# Relay_IO.net
KiCad netlist of a schematic drawn in Altium Designer
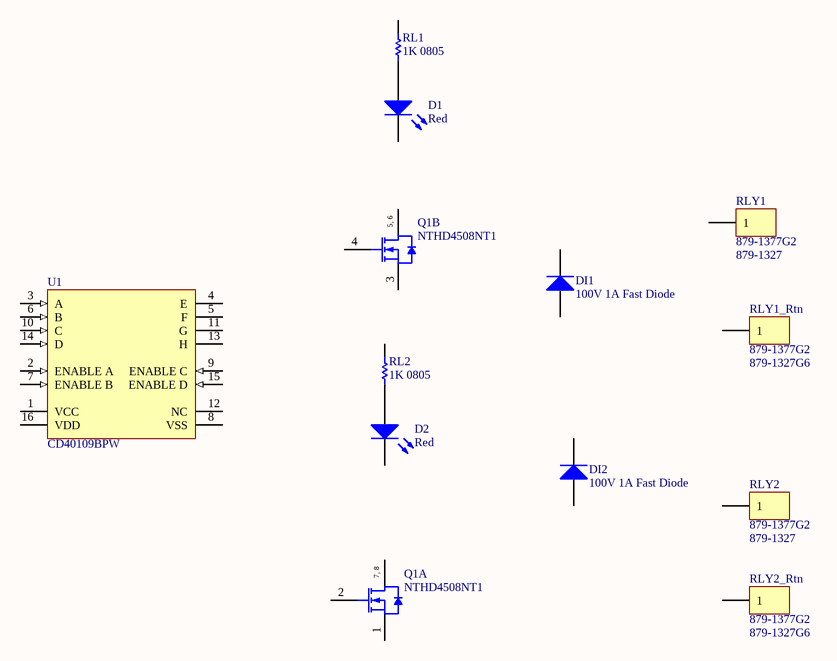
[diagram p0: Relay_IO.SchDoc]

(export (version "E")
  (design (tool "Eeschema 10.0.6"))
  (components
    (comp (ref "D1")
      (value "LED Red")
      (footprint "0603_A")
      (description "SMD mono-color Chip LED, WL-SMCW, Red")
      (fields
        (field (name "MANUFACTURER") "Wurth Electronics Inc")
        (field (name "MANUFACTURER PART NUMBER") "150060RS75000")
        (field (name "COLOR") "Red")
      )
      (libsource (lib "WCT") (part "LED_Red0603"))
    )
    (comp (ref "D2")
      (value "LED Red")
      (footprint "0603_A")
      (description "SMD mono-color Chip LED, WL-SMCW, Red")
      (fields
        (field (name "MANUFACTURER") "Wurth Electronics Inc")
        (field (name "MANUFACTURER PART NUMBER") "150060RS75000")
        (field (name "COLOR") "Red")
      )
      (libsource (lib "WCT") (part "LED_Red0603"))
    )
    (comp (ref "DI1")
      (value "100V 1A Fast Diode")
      (footprint "DO-35")
      (description "High Conductance Fast Diode")
      (fields
        (field (name "MANUFACTURER") "ON Semiconductor")
        (field (name "MANUFACTURER PART NUMBER") "MUR110RLG")
      )
      (libsource (lib "WCT") (part "Diode 1N4148"))
    )
    (comp (ref "DI2")
      (value "100V 1A Fast Diode")
      (footprint "DO-35")
      (description "High Conductance Fast Diode")
      (fields
        (field (name "MANUFACTURER") "ON Semiconductor")
        (field (name "MANUFACTURER PART NUMBER") "MUR110RLG")
      )
      (libsource (lib "WCT") (part "Diode 1N4148"))
    )
    (comp (ref "Q1")
      (value "NTHD4508NT1")
      (footprint "ONSC-CHIPFET-8-1206A-03_S2_V")
      (description "Power MOSFET, 20 V, 4.1 A, Dual N-Channel, 8-Pin CHIPFET, Tape and Reel")
      (fields (field (name "MANUFACTURER") "On Semiconductor"))
      (libsource (lib "Altium Content Vault") (part "ONSC-NNMOS-8_D"))
    )
    (comp (ref "RL1")
      (value "1K 0805")
      (footprint "0805_L")
      (fields
        (field (name "MANUFACTURER") "Panasonic Electronic Components")
        (field (name "MANUFACTURER PART NUMBER") "ERJ-6GEYJ102V")
        (field (name "TOLERANCE") "±5%")
      )
      (libsource (lib "WCT") (part "Res1K_0805"))
    )
    (comp (ref "RL2")
      (value "1K 0805")
      (footprint "0805_L")
      (fields
        (field (name "MANUFACTURER") "Panasonic Electronic Components")
        (field (name "MANUFACTURER PART NUMBER") "ERJ-6GEYJ102V")
        (field (name "TOLERANCE") "±5%")
      )
      (libsource (lib "WCT") (part "Res1K_0805"))
    )
    (comp (ref "RLY1")
      (value "Anderson-1Pin RED_PCB_RHT")
      (footprint "Anderson_Red_RHT_BOT")
      (description "1 pin Anderson")
      (fields
        (field (name "MANUFACTURER") "Anderson Power Products (APP)")
        (field (name "MANUFACTURER PART NUMBER") "1377G1, 1377G2, 1327-BK,137G6-BK")
        (field (name "SUPPLIER PART NUMBER 1") "879-1377G2")
        (field (name "SUPPLIER PART NUMBER 2") "879-1327")
      )
      (libsource (lib "WCT") (part "Anderson-1Pin RED_PCB_RHT"))
    )
    (comp (ref "RLY1_Rtn")
      (value "Anderson-1Pin BLK_PCB_RHT")
      (footprint "Anderson_BLK_RHT_BOT")
      (description "1 pin Anderson")
      (fields
        (field (name "MANUFACTURER") "Anderson Power Products (APP)")
        (field (name "MANUFACTURER PART NUMBER") "1377G1, 1377G2, 1327-BK,137G6-BK")
        (field (name "SUPPLIER PART NUMBER 1") "879-1377G2")
        (field (name "SUPPLIER PART NUMBER 2") "879-1327G6")
      )
      (libsource (lib "WCT") (part "Anderson-1Pin BLK_PCB_RHT"))
    )
    (comp (ref "RLY2")
      (value "Anderson-1Pin RED_PCB_RHT")
      (footprint "Anderson_Red_RHT_BOT")
      (description "1 pin Anderson")
      (fields
        (field (name "MANUFACTURER") "Anderson Power Products (APP)")
        (field (name "MANUFACTURER PART NUMBER") "1377G1, 1377G2, 1327-BK,137G6-BK")
        (field (name "SUPPLIER PART NUMBER 1") "879-1377G2")
        (field (name "SUPPLIER PART NUMBER 2") "879-1327")
      )
      (libsource (lib "WCT") (part "Anderson-1Pin RED_PCB_RHT"))
    )
    (comp (ref "RLY2_Rtn")
      (value "Anderson-1Pin BLK_PCB_RHT")
      (footprint "Anderson_BLK_RHT_BOT")
      (description "1 pin Anderson")
      (fields
        (field (name "MANUFACTURER") "Anderson Power Products (APP)")
        (field (name "MANUFACTURER PART NUMBER") "1377G1, 1377G2, 1327-BK,137G6-BK")
        (field (name "SUPPLIER PART NUMBER 1") "879-1377G2")
        (field (name "SUPPLIER PART NUMBER 2") "879-1327G6")
      )
      (libsource (lib "WCT") (part "Anderson-1Pin BLK_PCB_RHT"))
    )
    (comp (ref "U1")
      (value "CD40109BPW")
      (footprint "PW0016A_M")
      (fields (field (name "MANUFACTURER") "Texas Instruments"))
      (libsource (lib "Altium Content Vault") (part "TI-CD40109B-16"))
    )
  )
  (nets
    (net (code "1") (name "Net-(D1-A)") (class "Default")
      (node (ref "D1") (pin "2") (pinfunction "A_2") (pintype "passive"))
      (node (ref "RL1") (pin "1") (pinfunction "1_1") (pintype "passive"))
    )
    (net (code "2") (name "Net-(D2-A)") (class "Default")
      (node (ref "D2") (pin "2") (pinfunction "A_2") (pintype "passive"))
      (node (ref "RL2") (pin "1") (pinfunction "1_1") (pintype "passive"))
    )
    (net (code "3") (name "Net-(Q1A-D1-Pad7)") (class "Default")
      (node (ref "Q1") (pin "7") (pinfunction "D1_7") (pintype "passive"))
      (node (ref "Q1") (pin "8") (pinfunction "D1_8") (pintype "passive"))
    )
    (net (code "4") (name "Net-(Q1B-D2-Pad5)") (class "Default")
      (node (ref "Q1") (pin "5") (pinfunction "D2_5") (pintype "passive"))
      (node (ref "Q1") (pin "6") (pinfunction "D2_6") (pintype "passive"))
    )
    (net (code "5") (name "unconnected-(D1-K-Pad1)") (class "Default")
      (node (ref "D1") (pin "1") (pinfunction "K_1") (pintype "passive"))
    )
    (net (code "6") (name "unconnected-(D2-K-Pad1)") (class "Default")
      (node (ref "D2") (pin "1") (pinfunction "K_1") (pintype "passive"))
    )
    (net (code "7") (name "unconnected-(DI1-A-Pad1)") (class "Default")
      (node (ref "DI1") (pin "1") (pinfunction "A_1") (pintype "passive"))
    )
    (net (code "8") (name "unconnected-(DI1-K-Pad2)") (class "Default")
      (node (ref "DI1") (pin "2") (pinfunction "K_2") (pintype "passive"))
    )
    (net (code "9") (name "unconnected-(DI2-A-Pad1)") (class "Default")
      (node (ref "DI2") (pin "1") (pinfunction "A_1") (pintype "passive"))
    )
    (net (code "10") (name "unconnected-(DI2-K-Pad2)") (class "Default")
      (node (ref "DI2") (pin "2") (pinfunction "K_2") (pintype "passive"))
    )
    (net (code "11") (name "unconnected-(Q1A-G1-Pad2)") (class "Default")
      (node (ref "Q1") (pin "2") (pinfunction "G1_2") (pintype "passive"))
    )
    (net (code "12") (name "unconnected-(Q1A-S1-Pad1)") (class "Default")
      (node (ref "Q1") (pin "1") (pinfunction "S1_1") (pintype "passive"))
    )
    (net (code "13") (name "unconnected-(Q1B-G2-Pad4)") (class "Default")
      (node (ref "Q1") (pin "4") (pinfunction "G2_4") (pintype "passive"))
    )
    (net (code "14") (name "unconnected-(Q1B-S2-Pad3)") (class "Default")
      (node (ref "Q1") (pin "3") (pinfunction "S2_3") (pintype "passive"))
    )
    (net (code "15") (name "unconnected-(RL1-Pad2)") (class "Default")
      (node (ref "RL1") (pin "2") (pinfunction "2_2") (pintype "passive"))
    )
    (net (code "16") (name "unconnected-(RL2-Pad2)") (class "Default")
      (node (ref "RL2") (pin "2") (pinfunction "2_2") (pintype "passive"))
    )
    (net (code "17") (name "unconnected-(RLY1-Pad1)") (class "Default")
      (node (ref "RLY1") (pin "1") (pinfunction "1_1") (pintype "passive"))
    )
    (net (code "18") (name "unconnected-(RLY1_Rtn-Pad1)") (class "Default")
      (node (ref "RLY1_Rtn") (pin "1") (pinfunction "1_1") (pintype "passive"))
    )
    (net (code "19") (name "unconnected-(RLY2-Pad1)") (class "Default")
      (node (ref "RLY2") (pin "1") (pinfunction "1_1") (pintype "passive"))
    )
    (net (code "20") (name "unconnected-(RLY2_Rtn-Pad1)") (class "Default")
      (node (ref "RLY2_Rtn") (pin "1") (pinfunction "1_1") (pintype "passive"))
    )
    (net (code "21") (name "unconnected-(U1-A-Pad3)") (class "Default")
      (node (ref "U1") (pin "3") (pinfunction "A_3") (pintype "input"))
    )
    (net (code "22") (name "unconnected-(U1-B-Pad6)") (class "Default")
      (node (ref "U1") (pin "6") (pinfunction "B_6") (pintype "input"))
    )
    (net (code "23") (name "unconnected-(U1-C-Pad10)") (class "Default")
      (node (ref "U1") (pin "10") (pinfunction "C_10") (pintype "input"))
    )
    (net (code "24") (name "unconnected-(U1-D-Pad14)") (class "Default")
      (node (ref "U1") (pin "14") (pinfunction "D_14") (pintype "input"))
    )
    (net (code "25") (name "unconnected-(U1-E-Pad4)") (class "Default")
      (node (ref "U1") (pin "4") (pinfunction "E_4") (pintype "tri_state"))
    )
    (net (code "26") (name "unconnected-(U1-ENABLE_A-Pad2)") (class "Default")
      (node (ref "U1") (pin "2") (pinfunction "ENABLE_A_2") (pintype "input"))
    )
    (net (code "27") (name "unconnected-(U1-ENABLE_B-Pad7)") (class "Default")
      (node (ref "U1") (pin "7") (pinfunction "ENABLE_B_7") (pintype "input"))
    )
    (net (code "28") (name "unconnected-(U1-ENABLE_C-Pad9)") (class "Default")
      (node (ref "U1") (pin "9") (pinfunction "ENABLE_C_9") (pintype "input"))
    )
    (net (code "29") (name "unconnected-(U1-ENABLE_D-Pad15)") (class "Default")
      (node (ref "U1") (pin "15") (pinfunction "ENABLE_D_15") (pintype "input"))
    )
    (net (code "30") (name "unconnected-(U1-F-Pad5)") (class "Default")
      (node (ref "U1") (pin "5") (pinfunction "F_5") (pintype "tri_state"))
    )
    (net (code "31") (name "unconnected-(U1-G-Pad11)") (class "Default")
      (node (ref "U1") (pin "11") (pinfunction "G_11") (pintype "tri_state"))
    )
    (net (code "32") (name "unconnected-(U1-H-Pad13)") (class "Default")
      (node (ref "U1") (pin "13") (pinfunction "H_13") (pintype "tri_state"))
    )
    (net (code "33") (name "unconnected-(U1-NC-Pad12)") (class "Default")
      (node (ref "U1") (pin "12") (pinfunction "NC_12") (pintype "passive"))
    )
    (net (code "34") (name "unconnected-(U1-VCC-Pad1)") (class "Default")
      (node (ref "U1") (pin "1") (pinfunction "VCC_1") (pintype "power_in"))
    )
    (net (code "35") (name "unconnected-(U1-VDD-Pad16)") (class "Default")
      (node (ref "U1") (pin "16") (pinfunction "VDD_16") (pintype "power_in"))
    )
    (net (code "36") (name "unconnected-(U1-VSS-Pad8)") (class "Default")
      (node (ref "U1") (pin "8") (pinfunction "VSS_8") (pintype "power_in"))
    )
  )
)
